# R-G-B_LED_Module.net
KiCad netlist of a schematic drawn in Altium Designer
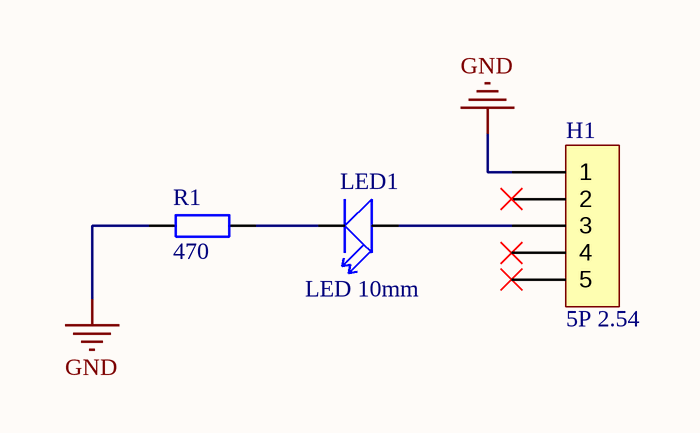
[diagram p0: R-G-B_LED Module.schdoc]

(export (version "E")
  (design (tool "Eeschema 10.0.6"))
  (components
    (comp (ref "H1")
      (value "5P 2.54")
      (footprint "Header 5P DC 2.54")
      (description "Cắm")
      (libsource (lib "namnt_Lib") (part "Header 5P 2.54 Duc Cong"))
    )
    (comp (ref "LED1")
      (value "LED 10mm")
      (footprint "LED2-2.54-D10MM")
      (description "304090142")
      (fields (field (name "MP") "DIP-LED-BLUE-BLUE-10MM(2P-D10MM)"))
      (libsource (lib "namnt_Lib") (part "LED 10mm"))
    )
    (comp (ref "R1")
      (value "470")
      (footprint "tro smd 0603")
      (description "Dán")
      (libsource (lib "namnt_Lib") (part "Tro 0603 5% 330R"))
    )
  )
  (nets
    (net (code "1") (name "GND") (class "Default")
      (node (ref "H1") (pin "1") (pinfunction "1_1") (pintype "passive"))
      (node (ref "R1") (pin "1") (pinfunction "1_1") (pintype "passive"))
    )
    (net (code "2") (name "Net-(H1-Pad3)") (class "Default")
      (node (ref "H1") (pin "3") (pinfunction "3_3") (pintype "passive"))
      (node (ref "LED1") (pin "POS") (pinfunction "POS_POS") (pintype "passive"))
    )
    (net (code "3") (name "Net-(LED1-PadNEG)") (class "Default")
      (node (ref "LED1") (pin "NEG") (pinfunction "NEG_NEG") (pintype "passive"))
      (node (ref "R1") (pin "2") (pinfunction "2_2") (pintype "passive"))
    )
    (net (code "4") (name "unconnected-(H1-Pad2)") (class "Default")
      (node (ref "H1") (pin "2") (pinfunction "2_2") (pintype "passive+no_connect"))
    )
    (net (code "5") (name "unconnected-(H1-Pad4)") (class "Default")
      (node (ref "H1") (pin "4") (pinfunction "4_4") (pintype "passive+no_connect"))
    )
    (net (code "6") (name "unconnected-(H1-Pad5)") (class "Default")
      (node (ref "H1") (pin "5") (pinfunction "5_5") (pintype "passive+no_connect"))
    )
  )
)
